# Power_Distribution_-_Output_from_Rear_Po.net
KiCad netlist of a schematic drawn in Altium Designer
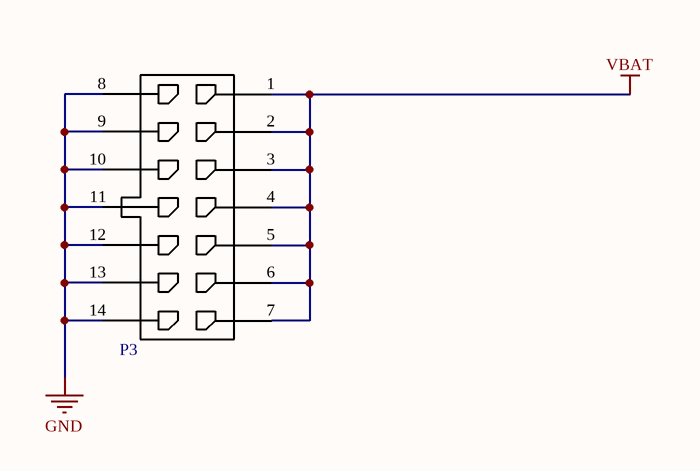
[diagram p0: Power Distribution - Output from Rear Power Distribution.SchDoc]

(export (version "E")
  (design (tool "Eeschema 10.0.6"))
  (components
    (comp (ref "P3")
      (value "CONN 14POS MICRO-FIT 3mm")
      (footprint "CONN, 14POS MICRO-FIT 3mm")
      (description "Connector Header Through Hole 14 position 0.118\" (3.00mm)")
      (fields
        (field (name "MANUFACTURER") "Molex, LLC")
        (field (name "MANUFACTURER PART NUMBER") "0430451427")
      )
      (libsource (lib "Schematic Diagrams") (part "CONN 14POS MICRO-FIT 3mm"))
    )
  )
  (nets
    (net (code "1") (name "GND") (class "Default")
      (node (ref "P3") (pin "10") (pinfunction "10_10") (pintype "passive"))
      (node (ref "P3") (pin "11") (pinfunction "11_11") (pintype "passive"))
      (node (ref "P3") (pin "12") (pinfunction "12_12") (pintype "passive"))
      (node (ref "P3") (pin "13") (pinfunction "13_13") (pintype "passive"))
      (node (ref "P3") (pin "14") (pinfunction "14_14") (pintype "passive"))
      (node (ref "P3") (pin "8") (pinfunction "8_8") (pintype "passive"))
      (node (ref "P3") (pin "9") (pinfunction "9_9") (pintype "passive"))
    )
    (net (code "2") (name "VBAT") (class "Default")
      (node (ref "P3") (pin "1") (pinfunction "1_1") (pintype "passive"))
      (node (ref "P3") (pin "2") (pinfunction "2_2") (pintype "passive"))
      (node (ref "P3") (pin "3") (pinfunction "3_3") (pintype "passive"))
      (node (ref "P3") (pin "4") (pinfunction "4_4") (pintype "passive"))
      (node (ref "P3") (pin "5") (pinfunction "5_5") (pintype "passive"))
      (node (ref "P3") (pin "6") (pinfunction "6_6") (pintype "passive"))
      (node (ref "P3") (pin "7") (pinfunction "7_7") (pintype "passive"))
    )
  )
)
